# 3-BitSelect.net
KiCad netlist of a schematic drawn in EAGLE
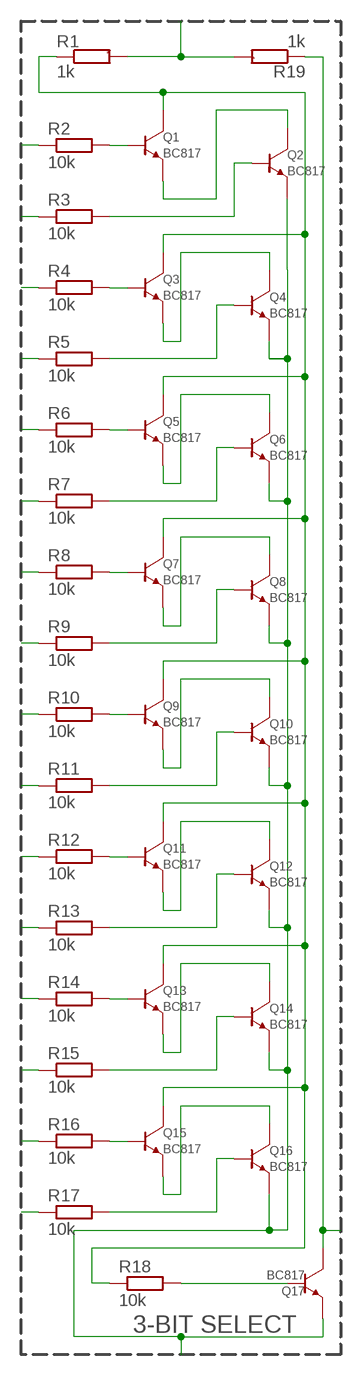
[diagram p0: schematic, sheet 1]

(export (version "E")
  (design (tool "Eeschema 10.0.6"))
  (components
    (comp (ref "Q1")
      (value "BC817")
      (footprint "eagle-import:SOT23")
      (libsource (lib "eagle-import") (part "TRANSISTOR-NPN-GENERIC-SOT23-BECDEFAULT"))
    )
    (comp (ref "Q2")
      (value "BC817")
      (footprint "eagle-import:SOT23")
      (libsource (lib "eagle-import") (part "TRANSISTOR-NPN-GENERIC-SOT23-BECDEFAULT"))
    )
    (comp (ref "Q3")
      (value "BC817")
      (footprint "eagle-import:SOT23")
      (libsource (lib "eagle-import") (part "TRANSISTOR-NPN-GENERIC-SOT23-BECDEFAULT"))
    )
    (comp (ref "Q4")
      (value "BC817")
      (footprint "eagle-import:SOT23")
      (libsource (lib "eagle-import") (part "TRANSISTOR-NPN-GENERIC-SOT23-BECDEFAULT"))
    )
    (comp (ref "Q5")
      (value "BC817")
      (footprint "eagle-import:SOT23")
      (libsource (lib "eagle-import") (part "TRANSISTOR-NPN-GENERIC-SOT23-BECDEFAULT"))
    )
    (comp (ref "Q6")
      (value "BC817")
      (footprint "eagle-import:SOT23")
      (libsource (lib "eagle-import") (part "TRANSISTOR-NPN-GENERIC-SOT23-BECDEFAULT"))
    )
    (comp (ref "Q7")
      (value "BC817")
      (footprint "eagle-import:SOT23")
      (libsource (lib "eagle-import") (part "TRANSISTOR-NPN-GENERIC-SOT23-BECDEFAULT"))
    )
    (comp (ref "Q8")
      (value "BC817")
      (footprint "eagle-import:SOT23")
      (libsource (lib "eagle-import") (part "TRANSISTOR-NPN-GENERIC-SOT23-BECDEFAULT"))
    )
    (comp (ref "Q9")
      (value "BC817")
      (footprint "eagle-import:SOT23")
      (libsource (lib "eagle-import") (part "TRANSISTOR-NPN-GENERIC-SOT23-BECDEFAULT"))
    )
    (comp (ref "Q10")
      (value "BC817")
      (footprint "eagle-import:SOT23")
      (libsource (lib "eagle-import") (part "TRANSISTOR-NPN-GENERIC-SOT23-BECDEFAULT"))
    )
    (comp (ref "Q11")
      (value "BC817")
      (footprint "eagle-import:SOT23")
      (libsource (lib "eagle-import") (part "TRANSISTOR-NPN-GENERIC-SOT23-BECDEFAULT"))
    )
    (comp (ref "Q12")
      (value "BC817")
      (footprint "eagle-import:SOT23")
      (libsource (lib "eagle-import") (part "TRANSISTOR-NPN-GENERIC-SOT23-BECDEFAULT"))
    )
    (comp (ref "Q13")
      (value "BC817")
      (footprint "eagle-import:SOT23")
      (libsource (lib "eagle-import") (part "TRANSISTOR-NPN-GENERIC-SOT23-BECDEFAULT"))
    )
    (comp (ref "Q14")
      (value "BC817")
      (footprint "eagle-import:SOT23")
      (libsource (lib "eagle-import") (part "TRANSISTOR-NPN-GENERIC-SOT23-BECDEFAULT"))
    )
    (comp (ref "Q15")
      (value "BC817")
      (footprint "eagle-import:SOT23")
      (libsource (lib "eagle-import") (part "TRANSISTOR-NPN-GENERIC-SOT23-BECDEFAULT"))
    )
    (comp (ref "Q16")
      (value "BC817")
      (footprint "eagle-import:SOT23")
      (libsource (lib "eagle-import") (part "TRANSISTOR-NPN-GENERIC-SOT23-BECDEFAULT"))
    )
    (comp (ref "Q17")
      (value "BC817")
      (footprint "eagle-import:SOT23")
      (libsource (lib "eagle-import") (part "TRANSISTOR-NPN-GENERIC-SOT23-BECDEFAULT"))
    )
    (comp (ref "R1")
      (value "1k")
      (footprint "eagle-import:R0603-MARK")
      (libsource (lib "eagle-import") (part "R-EU-MARKEDR0603"))
    )
    (comp (ref "R2")
      (value "10k")
      (footprint "eagle-import:R0603")
      (libsource (lib "eagle-import") (part "R-EU_R0603"))
    )
    (comp (ref "R3")
      (value "10k")
      (footprint "eagle-import:R0603")
      (libsource (lib "eagle-import") (part "R-EU_R0603"))
    )
    (comp (ref "R4")
      (value "10k")
      (footprint "eagle-import:R0603")
      (libsource (lib "eagle-import") (part "R-EU_R0603"))
    )
    (comp (ref "R5")
      (value "10k")
      (footprint "eagle-import:R0603")
      (libsource (lib "eagle-import") (part "R-EU_R0603"))
    )
    (comp (ref "R6")
      (value "10k")
      (footprint "eagle-import:R0603")
      (libsource (lib "eagle-import") (part "R-EU_R0603"))
    )
    (comp (ref "R7")
      (value "10k")
      (footprint "eagle-import:R0603")
      (libsource (lib "eagle-import") (part "R-EU_R0603"))
    )
    (comp (ref "R8")
      (value "10k")
      (footprint "eagle-import:R0603")
      (libsource (lib "eagle-import") (part "R-EU_R0603"))
    )
    (comp (ref "R9")
      (value "10k")
      (footprint "eagle-import:R0603")
      (libsource (lib "eagle-import") (part "R-EU_R0603"))
    )
    (comp (ref "R10")
      (value "10k")
      (footprint "eagle-import:R0603")
      (libsource (lib "eagle-import") (part "R-EU_R0603"))
    )
    (comp (ref "R11")
      (value "10k")
      (footprint "eagle-import:R0603")
      (libsource (lib "eagle-import") (part "R-EU_R0603"))
    )
    (comp (ref "R12")
      (value "10k")
      (footprint "eagle-import:R0603")
      (libsource (lib "eagle-import") (part "R-EU_R0603"))
    )
    (comp (ref "R13")
      (value "10k")
      (footprint "eagle-import:R0603")
      (libsource (lib "eagle-import") (part "R-EU_R0603"))
    )
    (comp (ref "R14")
      (value "10k")
      (footprint "eagle-import:R0603")
      (libsource (lib "eagle-import") (part "R-EU_R0603"))
    )
    (comp (ref "R15")
      (value "10k")
      (footprint "eagle-import:R0603")
      (libsource (lib "eagle-import") (part "R-EU_R0603"))
    )
    (comp (ref "R16")
      (value "10k")
      (footprint "eagle-import:R0603")
      (libsource (lib "eagle-import") (part "R-EU_R0603"))
    )
    (comp (ref "R17")
      (value "10k")
      (footprint "eagle-import:R0603")
      (libsource (lib "eagle-import") (part "R-EU_R0603"))
    )
    (comp (ref "R18")
      (value "10k")
      (footprint "eagle-import:R0603")
      (libsource (lib "eagle-import") (part "R-EU_R0603"))
    )
    (comp (ref "R19")
      (value "1k")
      (footprint "eagle-import:R0603-MARK")
      (libsource (lib "eagle-import") (part "R-EU-MARKEDR0603"))
    )
  )
  (nets
    (net (code "1") (name "Net-(Q1-BASE)") (class "Default")
      (node (ref "Q1") (pin "P$1") (pinfunction "BASE_P$1") (pintype "bidirectional"))
      (node (ref "R2") (pin "2") (pinfunction "2_2") (pintype "passive"))
    )
    (net (code "2") (name "Net-(Q1-COLLECTOR)") (class "Default")
      (node (ref "Q1") (pin "P$3") (pinfunction "COLLECTOR_P$3") (pintype "bidirectional"))
      (node (ref "Q11") (pin "P$3") (pinfunction "COLLECTOR_P$3") (pintype "bidirectional"))
      (node (ref "Q13") (pin "P$3") (pinfunction "COLLECTOR_P$3") (pintype "bidirectional"))
      (node (ref "Q15") (pin "P$3") (pinfunction "COLLECTOR_P$3") (pintype "bidirectional"))
      (node (ref "Q3") (pin "P$3") (pinfunction "COLLECTOR_P$3") (pintype "bidirectional"))
      (node (ref "Q5") (pin "P$3") (pinfunction "COLLECTOR_P$3") (pintype "bidirectional"))
      (node (ref "Q7") (pin "P$3") (pinfunction "COLLECTOR_P$3") (pintype "bidirectional"))
      (node (ref "Q9") (pin "P$3") (pinfunction "COLLECTOR_P$3") (pintype "bidirectional"))
      (node (ref "R1") (pin "1") (pinfunction "1_1") (pintype "passive"))
      (node (ref "R18") (pin "1") (pinfunction "1_1") (pintype "passive"))
    )
    (net (code "3") (name "Net-(Q1-EMITTER)") (class "Default")
      (node (ref "Q1") (pin "P$2") (pinfunction "EMITTER_P$2") (pintype "bidirectional"))
      (node (ref "Q2") (pin "P$3") (pinfunction "COLLECTOR_P$3") (pintype "bidirectional"))
    )
    (net (code "4") (name "Net-(Q2-BASE)") (class "Default")
      (node (ref "Q2") (pin "P$1") (pinfunction "BASE_P$1") (pintype "bidirectional"))
      (node (ref "R3") (pin "2") (pinfunction "2_2") (pintype "passive"))
    )
    (net (code "5") (name "Net-(Q3-BASE)") (class "Default")
      (node (ref "Q3") (pin "P$1") (pinfunction "BASE_P$1") (pintype "bidirectional"))
      (node (ref "R4") (pin "2") (pinfunction "2_2") (pintype "passive"))
    )
    (net (code "6") (name "Net-(Q3-EMITTER)") (class "Default")
      (node (ref "Q3") (pin "P$2") (pinfunction "EMITTER_P$2") (pintype "bidirectional"))
      (node (ref "Q4") (pin "P$3") (pinfunction "COLLECTOR_P$3") (pintype "bidirectional"))
    )
    (net (code "7") (name "Net-(Q4-BASE)") (class "Default")
      (node (ref "Q4") (pin "P$1") (pinfunction "BASE_P$1") (pintype "bidirectional"))
      (node (ref "R5") (pin "2") (pinfunction "2_2") (pintype "passive"))
    )
    (net (code "8") (name "Net-(Q5-BASE)") (class "Default")
      (node (ref "Q5") (pin "P$1") (pinfunction "BASE_P$1") (pintype "bidirectional"))
      (node (ref "R6") (pin "2") (pinfunction "2_2") (pintype "passive"))
    )
    (net (code "9") (name "Net-(Q5-EMITTER)") (class "Default")
      (node (ref "Q5") (pin "P$2") (pinfunction "EMITTER_P$2") (pintype "bidirectional"))
      (node (ref "Q6") (pin "P$3") (pinfunction "COLLECTOR_P$3") (pintype "bidirectional"))
    )
    (net (code "10") (name "Net-(Q6-BASE)") (class "Default")
      (node (ref "Q6") (pin "P$1") (pinfunction "BASE_P$1") (pintype "bidirectional"))
      (node (ref "R7") (pin "2") (pinfunction "2_2") (pintype "passive"))
    )
    (net (code "11") (name "Net-(Q7-BASE)") (class "Default")
      (node (ref "Q7") (pin "P$1") (pinfunction "BASE_P$1") (pintype "bidirectional"))
      (node (ref "R8") (pin "2") (pinfunction "2_2") (pintype "passive"))
    )
    (net (code "12") (name "Net-(Q7-EMITTER)") (class "Default")
      (node (ref "Q7") (pin "P$2") (pinfunction "EMITTER_P$2") (pintype "bidirectional"))
      (node (ref "Q8") (pin "P$3") (pinfunction "COLLECTOR_P$3") (pintype "bidirectional"))
    )
    (net (code "13") (name "Net-(Q8-BASE)") (class "Default")
      (node (ref "Q8") (pin "P$1") (pinfunction "BASE_P$1") (pintype "bidirectional"))
      (node (ref "R9") (pin "2") (pinfunction "2_2") (pintype "passive"))
    )
    (net (code "14") (name "Net-(Q9-BASE)") (class "Default")
      (node (ref "Q9") (pin "P$1") (pinfunction "BASE_P$1") (pintype "bidirectional"))
      (node (ref "R10") (pin "2") (pinfunction "2_2") (pintype "passive"))
    )
    (net (code "15") (name "Net-(Q10-BASE)") (class "Default")
      (node (ref "Q10") (pin "P$1") (pinfunction "BASE_P$1") (pintype "bidirectional"))
      (node (ref "R11") (pin "2") (pinfunction "2_2") (pintype "passive"))
    )
    (net (code "16") (name "Net-(Q10-COLLECTOR)") (class "Default")
      (node (ref "Q10") (pin "P$3") (pinfunction "COLLECTOR_P$3") (pintype "bidirectional"))
      (node (ref "Q9") (pin "P$2") (pinfunction "EMITTER_P$2") (pintype "bidirectional"))
    )
    (net (code "17") (name "Net-(Q10-EMITTER)") (class "Default")
      (node (ref "Q10") (pin "P$2") (pinfunction "EMITTER_P$2") (pintype "bidirectional"))
      (node (ref "Q12") (pin "P$2") (pinfunction "EMITTER_P$2") (pintype "bidirectional"))
      (node (ref "Q14") (pin "P$2") (pinfunction "EMITTER_P$2") (pintype "bidirectional"))
      (node (ref "Q16") (pin "P$2") (pinfunction "EMITTER_P$2") (pintype "bidirectional"))
      (node (ref "Q17") (pin "P$2") (pinfunction "EMITTER_P$2") (pintype "bidirectional"))
      (node (ref "Q2") (pin "P$2") (pinfunction "EMITTER_P$2") (pintype "bidirectional"))
      (node (ref "Q4") (pin "P$2") (pinfunction "EMITTER_P$2") (pintype "bidirectional"))
      (node (ref "Q6") (pin "P$2") (pinfunction "EMITTER_P$2") (pintype "bidirectional"))
      (node (ref "Q8") (pin "P$2") (pinfunction "EMITTER_P$2") (pintype "bidirectional"))
    )
    (net (code "18") (name "Net-(Q11-BASE)") (class "Default")
      (node (ref "Q11") (pin "P$1") (pinfunction "BASE_P$1") (pintype "bidirectional"))
      (node (ref "R12") (pin "2") (pinfunction "2_2") (pintype "passive"))
    )
    (net (code "19") (name "Net-(Q11-EMITTER)") (class "Default")
      (node (ref "Q11") (pin "P$2") (pinfunction "EMITTER_P$2") (pintype "bidirectional"))
      (node (ref "Q12") (pin "P$3") (pinfunction "COLLECTOR_P$3") (pintype "bidirectional"))
    )
    (net (code "20") (name "Net-(Q12-BASE)") (class "Default")
      (node (ref "Q12") (pin "P$1") (pinfunction "BASE_P$1") (pintype "bidirectional"))
      (node (ref "R13") (pin "2") (pinfunction "2_2") (pintype "passive"))
    )
    (net (code "21") (name "Net-(Q13-BASE)") (class "Default")
      (node (ref "Q13") (pin "P$1") (pinfunction "BASE_P$1") (pintype "bidirectional"))
      (node (ref "R14") (pin "2") (pinfunction "2_2") (pintype "passive"))
    )
    (net (code "22") (name "Net-(Q13-EMITTER)") (class "Default")
      (node (ref "Q13") (pin "P$2") (pinfunction "EMITTER_P$2") (pintype "bidirectional"))
      (node (ref "Q14") (pin "P$3") (pinfunction "COLLECTOR_P$3") (pintype "bidirectional"))
    )
    (net (code "23") (name "Net-(Q14-BASE)") (class "Default")
      (node (ref "Q14") (pin "P$1") (pinfunction "BASE_P$1") (pintype "bidirectional"))
      (node (ref "R15") (pin "2") (pinfunction "2_2") (pintype "passive"))
    )
    (net (code "24") (name "Net-(Q15-BASE)") (class "Default")
      (node (ref "Q15") (pin "P$1") (pinfunction "BASE_P$1") (pintype "bidirectional"))
      (node (ref "R16") (pin "2") (pinfunction "2_2") (pintype "passive"))
    )
    (net (code "25") (name "Net-(Q15-EMITTER)") (class "Default")
      (node (ref "Q15") (pin "P$2") (pinfunction "EMITTER_P$2") (pintype "bidirectional"))
      (node (ref "Q16") (pin "P$3") (pinfunction "COLLECTOR_P$3") (pintype "bidirectional"))
    )
    (net (code "26") (name "Net-(Q16-BASE)") (class "Default")
      (node (ref "Q16") (pin "P$1") (pinfunction "BASE_P$1") (pintype "bidirectional"))
      (node (ref "R17") (pin "2") (pinfunction "2_2") (pintype "passive"))
    )
    (net (code "27") (name "Net-(Q17-BASE)") (class "Default")
      (node (ref "Q17") (pin "P$1") (pinfunction "BASE_P$1") (pintype "bidirectional"))
      (node (ref "R18") (pin "2") (pinfunction "2_2") (pintype "passive"))
    )
    (net (code "28") (name "Net-(Q17-COLLECTOR)") (class "Default")
      (node (ref "Q17") (pin "P$3") (pinfunction "COLLECTOR_P$3") (pintype "bidirectional"))
      (node (ref "R19") (pin "1") (pinfunction "1_1") (pintype "passive"))
    )
    (net (code "29") (name "Net-(R1-Pad2)") (class "Default")
      (node (ref "R1") (pin "2") (pinfunction "2_2") (pintype "passive"))
      (node (ref "R19") (pin "2") (pinfunction "2_2") (pintype "passive"))
    )
    (net (code "30") (name "unconnected-(R2-Pad1)") (class "Default")
      (node (ref "R2") (pin "1") (pinfunction "1_1") (pintype "passive"))
    )
    (net (code "31") (name "unconnected-(R3-Pad1)") (class "Default")
      (node (ref "R3") (pin "1") (pinfunction "1_1") (pintype "passive"))
    )
    (net (code "32") (name "unconnected-(R4-Pad1)") (class "Default")
      (node (ref "R4") (pin "1") (pinfunction "1_1") (pintype "passive"))
    )
    (net (code "33") (name "unconnected-(R5-Pad1)") (class "Default")
      (node (ref "R5") (pin "1") (pinfunction "1_1") (pintype "passive"))
    )
    (net (code "34") (name "unconnected-(R6-Pad1)") (class "Default")
      (node (ref "R6") (pin "1") (pinfunction "1_1") (pintype "passive"))
    )
    (net (code "35") (name "unconnected-(R7-Pad1)") (class "Default")
      (node (ref "R7") (pin "1") (pinfunction "1_1") (pintype "passive"))
    )
    (net (code "36") (name "unconnected-(R8-Pad1)") (class "Default")
      (node (ref "R8") (pin "1") (pinfunction "1_1") (pintype "passive"))
    )
    (net (code "37") (name "unconnected-(R9-Pad1)") (class "Default")
      (node (ref "R9") (pin "1") (pinfunction "1_1") (pintype "passive"))
    )
    (net (code "38") (name "unconnected-(R10-Pad1)") (class "Default")
      (node (ref "R10") (pin "1") (pinfunction "1_1") (pintype "passive"))
    )
    (net (code "39") (name "unconnected-(R11-Pad1)") (class "Default")
      (node (ref "R11") (pin "1") (pinfunction "1_1") (pintype "passive"))
    )
    (net (code "40") (name "unconnected-(R12-Pad1)") (class "Default")
      (node (ref "R12") (pin "1") (pinfunction "1_1") (pintype "passive"))
    )
    (net (code "41") (name "unconnected-(R13-Pad1)") (class "Default")
      (node (ref "R13") (pin "1") (pinfunction "1_1") (pintype "passive"))
    )
    (net (code "42") (name "unconnected-(R14-Pad1)") (class "Default")
      (node (ref "R14") (pin "1") (pinfunction "1_1") (pintype "passive"))
    )
    (net (code "43") (name "unconnected-(R15-Pad1)") (class "Default")
      (node (ref "R15") (pin "1") (pinfunction "1_1") (pintype "passive"))
    )
    (net (code "44") (name "unconnected-(R16-Pad1)") (class "Default")
      (node (ref "R16") (pin "1") (pinfunction "1_1") (pintype "passive"))
    )
    (net (code "45") (name "unconnected-(R17-Pad1)") (class "Default")
      (node (ref "R17") (pin "1") (pinfunction "1_1") (pintype "passive"))
    )
  )
)
